# STM32F7.net
KiCad netlist of a schematic drawn in Altium Designer
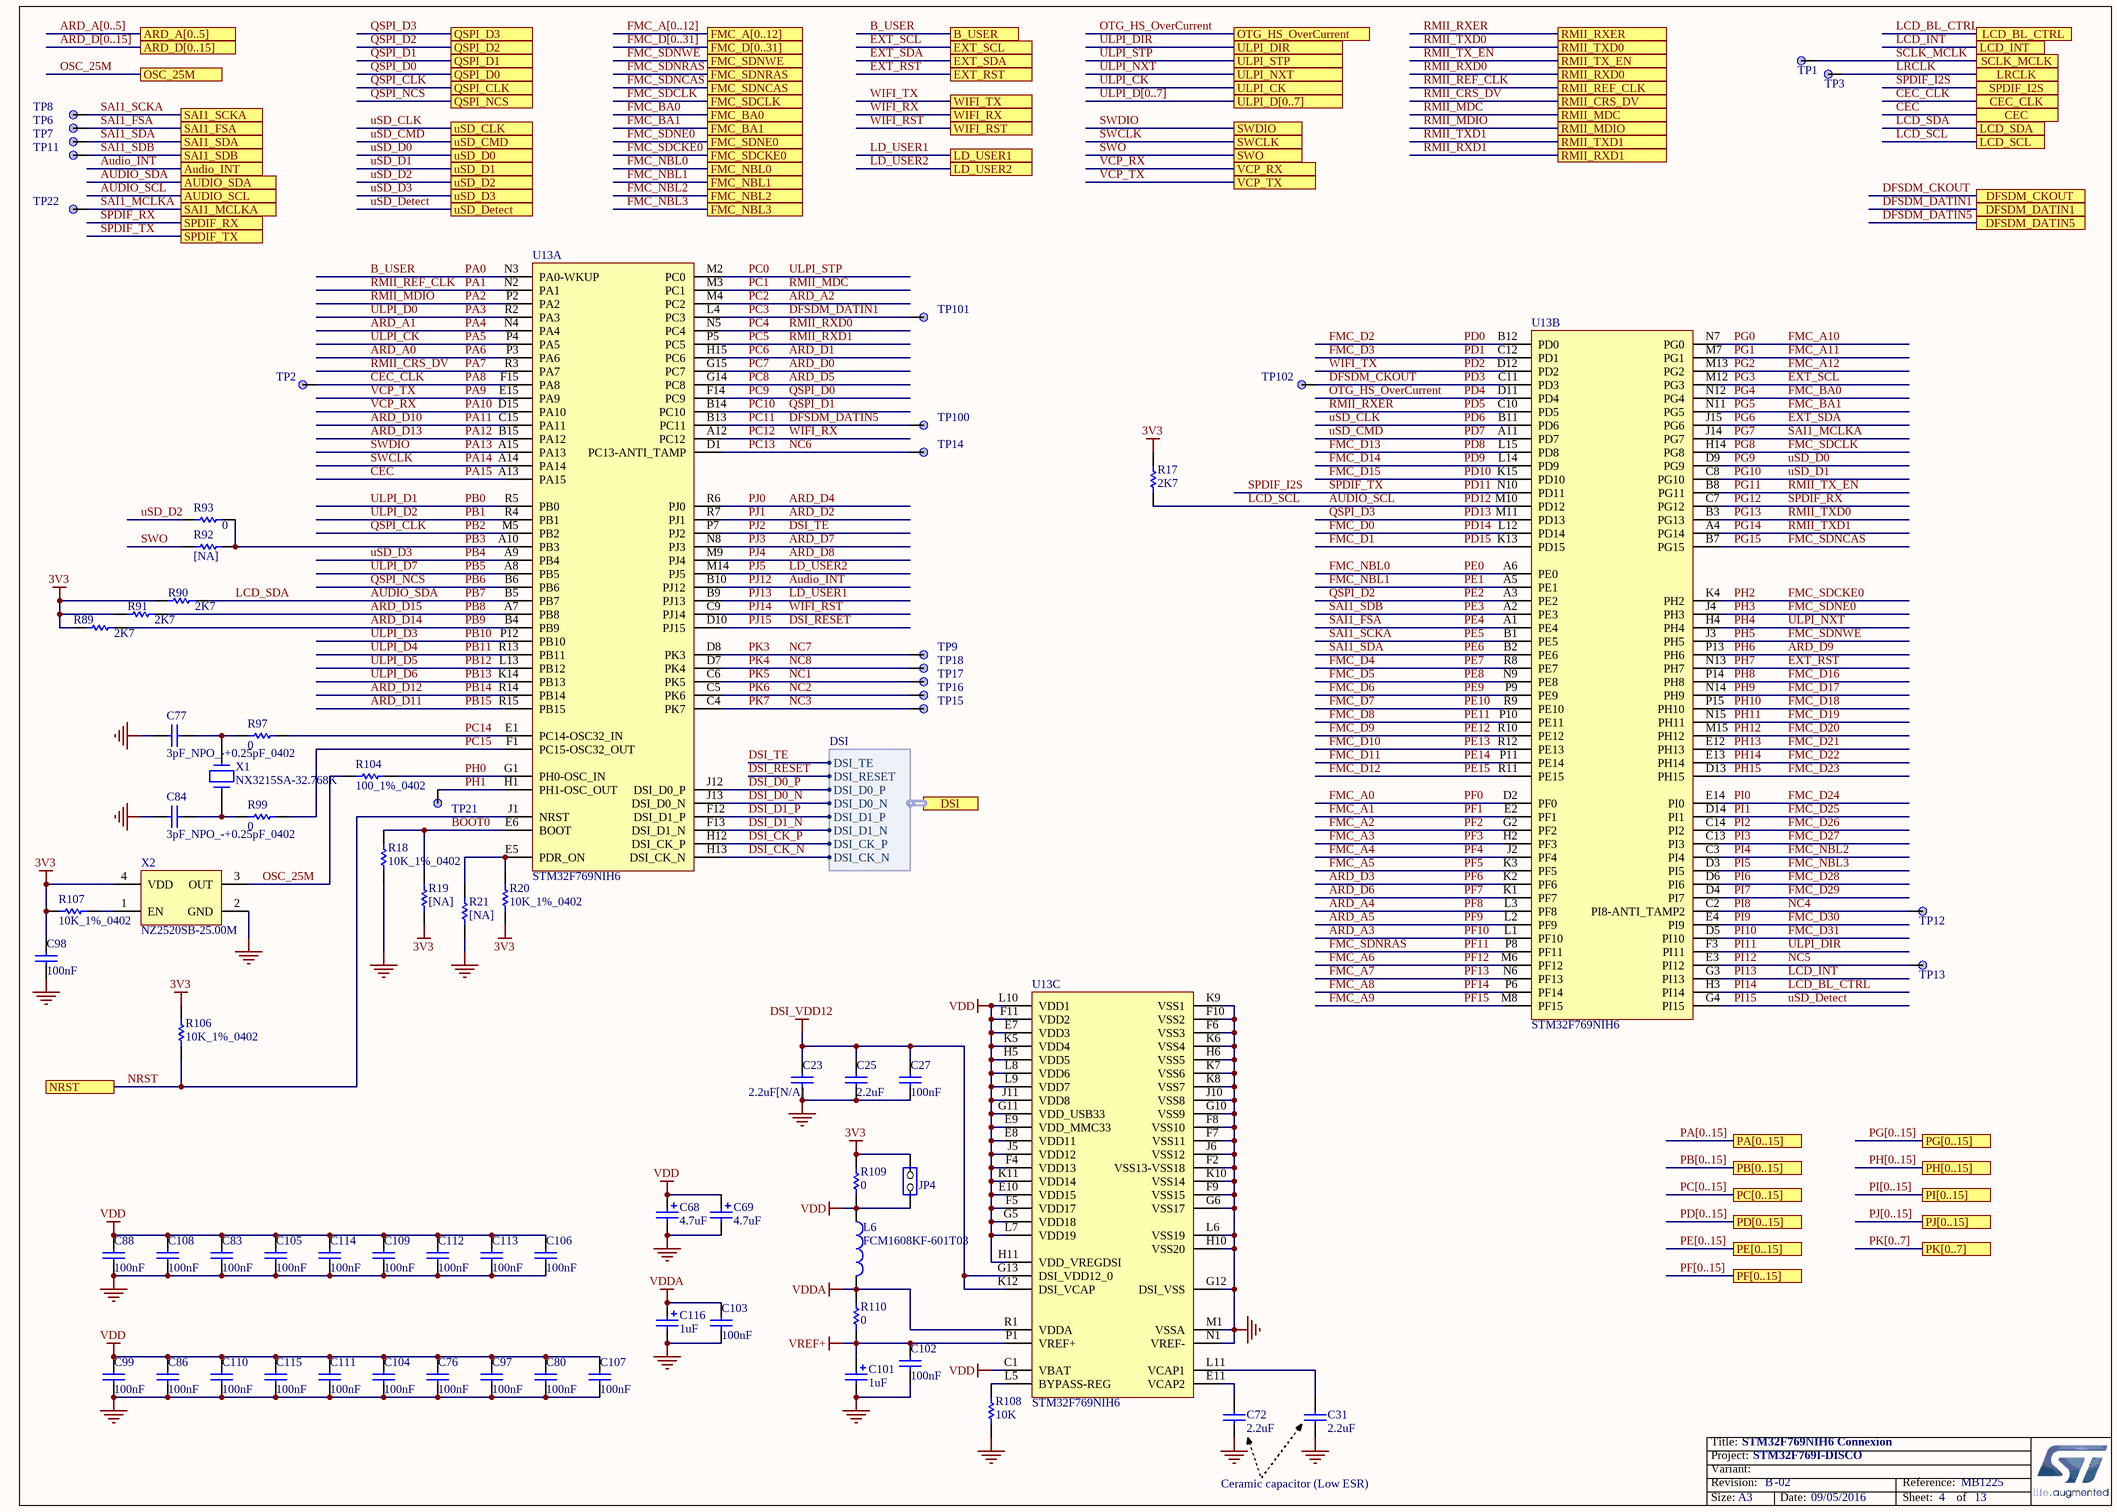
[diagram p0: STM32F7.SchDoc]

(export (version "E")
  (design (tool "Eeschema 10.0.6"))
  (components
    (comp (ref "C23")
      (value "2.2uF[N/A]")
      (footprint "1206C")
      (description "Capacitor,2.2uF,16V, X7R,10%,1206,YAGEO")
      (libsource (lib "MCD_TOOLS_CAPACITOR") (part "Cap_2.2uF_X7R_10%_1206"))
    )
    (comp (ref "C25")
      (value "2.2uF")
      (footprint "0603C")
      (description "Capacitor,2.2uF,10V, X5R,10%,0603,YAGEO")
      (libsource (lib "MCD_TOOLS_CAPACITOR") (part "Cap_2.2uF_X5R_10%_0603"))
    )
    (comp (ref "C27")
      (value "100nF")
      (footprint "0402C")
      (description "Capacitor,100nF,16V,X7R,10%,0402,YAGEO")
      (libsource (lib "MCD_TOOLS_CAPACITOR") (part "Cap_100nF_X7R_10%_0402"))
    )
    (comp (ref "C31")
      (value "2.2uF")
      (footprint "1206C")
      (description "Capacitor,2.2uF,16V, X7R,10%,1206,YAGEO")
      (libsource (lib "MCD_TOOLS") (part "Cap_2.2uF_X7R_10%_1206"))
    )
    (comp (ref "C68")
      (value "4.7uF")
      (footprint "TAN-A")
      (description "Polarized Capacitor,4.7uF,16V,10%,typeA,AVX")
      (libsource (lib "MCD_TOOLS") (part "Cap_4.7uF_POL_10%_TANA"))
    )
    (comp (ref "C69")
      (value "4.7uF")
      (footprint "TAN-A")
      (description "Polarized Capacitor,4.7uF,16V,10%,typeA,AVX")
      (libsource (lib "MCD_TOOLS") (part "Cap_4.7uF_POL_10%_TANA"))
    )
    (comp (ref "C72")
      (value "2.2uF")
      (footprint "1206C")
      (description "Capacitor,2.2uF,16V, X7R,10%,1206,YAGEO")
      (libsource (lib "MCD_TOOLS") (part "Cap_2.2uF_X7R_10%_1206"))
    )
    (comp (ref "C76")
      (value "100nF")
      (footprint "0402C")
      (description "Capacitor,100nF,16V,X7R,10%,0402,YAGEO")
      (libsource (lib "MCD_TOOLS") (part "Cap_100nF_X7R_10%_0402"))
    )
    (comp (ref "C77")
      (value "3pF_NPO_-+0.25pF_0402")
      (footprint "0402C")
      (description "Capacitor, 3pF, 16V, NPO, -+0.25pF, 0402, KEMET")
      (libsource (lib "MCD_TOOLS_CAPACITOR") (part "Cap_4.3pF_NPO_-+0.25pF_0402"))
    )
    (comp (ref "C80")
      (value "100nF")
      (footprint "0402C")
      (description "Capacitor,100nF,16V,X7R,10%,0402,YAGEO")
      (libsource (lib "MCD_TOOLS") (part "Cap_100nF_X7R_10%_0402"))
    )
    (comp (ref "C83")
      (value "100nF")
      (footprint "0402C")
      (description "Capacitor,100nF,16V,X7R,10%,0402,YAGEO")
      (libsource (lib "MCD_TOOLS") (part "Cap_100nF_X7R_10%_0402"))
    )
    (comp (ref "C84")
      (value "3pF_NPO_-+0.25pF_0402")
      (footprint "0402C")
      (description "Capacitor, 3pF, 16V, NPO, -+0.25pF, 0402, KEMET")
      (libsource (lib "MCD_TOOLS_CAPACITOR") (part "Cap_4.3pF_NPO_-+0.25pF_0402"))
    )
    (comp (ref "C86")
      (value "100nF")
      (footprint "0402C")
      (description "Capacitor,100nF,16V,X7R,10%,0402,YAGEO")
      (libsource (lib "MCD_TOOLS") (part "Cap_100nF_X7R_10%_0402"))
    )
    (comp (ref "C88")
      (value "100nF")
      (footprint "0402C")
      (description "Capacitor,100nF,16V,X7R,10%,0402,YAGEO")
      (libsource (lib "MCD_TOOLS") (part "Cap_100nF_X7R_10%_0402"))
    )
    (comp (ref "C97")
      (value "100nF")
      (footprint "0402C")
      (description "Capacitor,100nF,16V,X7R,10%,0402,YAGEO")
      (libsource (lib "MCD_TOOLS") (part "Cap_100nF_X7R_10%_0402"))
    )
    (comp (ref "C98")
      (value "100nF")
      (footprint "0402C")
      (description "Capacitor,100nF,16V,X7R,10%,0402,YAGEO")
      (libsource (lib "MCD_TOOLS") (part "Cap_100nF_X7R_10%_0402"))
    )
    (comp (ref "C99")
      (value "100nF")
      (footprint "0402C")
      (description "Capacitor,100nF,16V,X7R,10%,0402,YAGEO")
      (libsource (lib "MCD_TOOLS") (part "Cap_100nF_X7R_10%_0402"))
    )
    (comp (ref "C101")
      (value "1uF")
      (footprint "TAN-A")
      (description "Polarized Capacitor,1uF,16V,10%,typeA,AVX")
      (libsource (lib "MCD_TOOLS") (part "Cap_1uF_POL_10%_TANA"))
    )
    (comp (ref "C102")
      (value "100nF")
      (footprint "0402C")
      (description "Capacitor,100nF,16V,X7R,10%,0402,YAGEO")
      (libsource (lib "MCD_TOOLS") (part "Cap_100nF_X7R_10%_0402"))
    )
    (comp (ref "C103")
      (value "100nF")
      (footprint "0402C")
      (description "Capacitor,100nF,16V,X7R,10%,0402,YAGEO")
      (libsource (lib "MCD_TOOLS") (part "Cap_100nF_X7R_10%_0402"))
    )
    (comp (ref "C104")
      (value "100nF")
      (footprint "0402C")
      (description "Capacitor,100nF,16V,X7R,10%,0402,YAGEO")
      (libsource (lib "MCD_TOOLS") (part "Cap_100nF_X7R_10%_0402"))
    )
    (comp (ref "C105")
      (value "100nF")
      (footprint "0402C")
      (description "Capacitor,100nF,16V,X7R,10%,0402,YAGEO")
      (libsource (lib "MCD_TOOLS") (part "Cap_100nF_X7R_10%_0402"))
    )
    (comp (ref "C106")
      (value "100nF")
      (footprint "0402C")
      (description "Capacitor,100nF,16V,X7R,10%,0402,YAGEO")
      (libsource (lib "MCD_TOOLS") (part "Cap_100nF_X7R_10%_0402"))
    )
    (comp (ref "C107")
      (value "100nF")
      (footprint "0402C")
      (description "Capacitor,100nF,16V,X7R,10%,0402,YAGEO")
      (libsource (lib "MCD_TOOLS") (part "Cap_100nF_X7R_10%_0402"))
    )
    (comp (ref "C108")
      (value "100nF")
      (footprint "0402C")
      (description "Capacitor,100nF,16V,X7R,10%,0402,YAGEO")
      (libsource (lib "MCD_TOOLS") (part "Cap_100nF_X7R_10%_0402"))
    )
    (comp (ref "C109")
      (value "100nF")
      (footprint "0402C")
      (description "Capacitor,100nF,16V,X7R,10%,0402,YAGEO")
      (libsource (lib "MCD_TOOLS") (part "Cap_100nF_X7R_10%_0402"))
    )
    (comp (ref "C110")
      (value "100nF")
      (footprint "0402C")
      (description "Capacitor,100nF,16V,X7R,10%,0402,YAGEO")
      (libsource (lib "MCD_TOOLS") (part "Cap_100nF_X7R_10%_0402"))
    )
    (comp (ref "C111")
      (value "100nF")
      (footprint "0402C")
      (description "Capacitor,100nF,16V,X7R,10%,0402,YAGEO")
      (libsource (lib "MCD_TOOLS") (part "Cap_100nF_X7R_10%_0402"))
    )
    (comp (ref "C112")
      (value "100nF")
      (footprint "0402C")
      (description "Capacitor,100nF,16V,X7R,10%,0402,YAGEO")
      (libsource (lib "MCD_TOOLS") (part "Cap_100nF_X7R_10%_0402"))
    )
    (comp (ref "C113")
      (value "100nF")
      (footprint "0402C")
      (description "Capacitor,100nF,16V,X7R,10%,0402,YAGEO")
      (libsource (lib "MCD_TOOLS") (part "Cap_100nF_X7R_10%_0402"))
    )
    (comp (ref "C114")
      (value "100nF")
      (footprint "0402C")
      (description "Capacitor,100nF,16V,X7R,10%,0402,YAGEO")
      (libsource (lib "MCD_TOOLS") (part "Cap_100nF_X7R_10%_0402"))
    )
    (comp (ref "C115")
      (value "100nF")
      (footprint "0402C")
      (description "Capacitor,100nF,16V,X7R,10%,0402,YAGEO")
      (libsource (lib "MCD_TOOLS") (part "Cap_100nF_X7R_10%_0402"))
    )
    (comp (ref "C116")
      (value "1uF")
      (footprint "TAN-A")
      (description "Polarized Capacitor,1uF,16V,10%,typeA,AVX")
      (libsource (lib "MCD_TOOLS") (part "Cap_1uF_POL_10%_TANA"))
    )
    (comp (ref "JP4") (value "JP2") (footprint "SIP2") (libsource (lib "MCD_TOOLS_CONNECTOR") (part "JP2")))
    (comp (ref "L6")
      (value "FCM1608KF-601T03")
      (footprint "0603L")
      (description "Bead,600R,350mA,0603,FCM1608KF-601T03,Tai-tech")
      (libsource (lib "MCD_TOOLS") (part "BEAD_600R_350MA_0603"))
    )
    (comp (ref "R17")
      (value "2K7")
      (footprint "0402R")
      (description "Resistor,2K7,0402,1%,YAGEO")
      (libsource (lib "MCD_TOOLS") (part "Res_2K7_1%_0402"))
    )
    (comp (ref "R18")
      (value "10K_1%_0402")
      (footprint "0402R")
      (description "Resistor,10K,0402,1%,YAGEO")
      (libsource (lib "MCD_TOOLS") (part "Res_10K_1%_0402"))
    )
    (comp (ref "R19")
      (value "[NA]")
      (footprint "0402R")
      (description "Resistor,[NA],0402")
      (libsource (lib "MCD_TOOLS") (part "Res_NA_0402"))
    )
    (comp (ref "R20")
      (value "10K_1%_0402")
      (footprint "0402R")
      (description "Resistor,10K,0402,1%,YAGEO")
      (libsource (lib "MCD_TOOLS") (part "Res_10K_1%_0402"))
    )
    (comp (ref "R21")
      (value "[NA]")
      (footprint "0402R")
      (description "Resistor,[NA],0402")
      (libsource (lib "MCD_TOOLS") (part "Res_NA_0402"))
    )
    (comp (ref "R89")
      (value "2K7")
      (footprint "0402R")
      (description "Resistor,2K7,0402,1%,YAGEO")
      (libsource (lib "MCD_TOOLS") (part "Res_2K7_1%_0402"))
    )
    (comp (ref "R90")
      (value "2K7")
      (footprint "0402R")
      (description "Resistor,2K7,0402,1%,YAGEO")
      (libsource (lib "MCD_TOOLS") (part "Res_2K7_1%_0402"))
    )
    (comp (ref "R91")
      (value "2K7")
      (footprint "0402R")
      (description "Resistor,2K7,0402,1%,YAGEO")
      (libsource (lib "MCD_TOOLS") (part "Res_2K7_1%_0402"))
    )
    (comp (ref "R92")
      (value "[NA]")
      (footprint "0402R")
      (description "Resistor,[NA],0402")
      (libsource (lib "MCD_TOOLS_RESISTOR") (part "Res_NA_0402"))
    )
    (comp (ref "R93")
      (value "0")
      (footprint "0402R")
      (description "Resistor,0,0402,5%,YAGEO")
      (libsource (lib "MCD_TOOLS_RESISTOR") (part "Res_0_5%_0402"))
    )
    (comp (ref "R97")
      (value "0")
      (footprint "0402R")
      (description "Resistor,0,0402,5%,YAGEO")
      (libsource (lib "MCD_TOOLS") (part "Res_0_5%_0402"))
    )
    (comp (ref "R99")
      (value "0")
      (footprint "0402R")
      (description "Resistor,0,0402,5%,YAGEO")
      (libsource (lib "MCD_TOOLS") (part "Res_0_5%_0402"))
    )
    (comp (ref "R104")
      (value "100_1%_0402")
      (footprint "0402R")
      (description "Resistor,100,0402,1%,YAGEO")
      (libsource (lib "MCD_TOOLS") (part "Res_100_1%_0402"))
    )
    (comp (ref "R106")
      (value "10K_1%_0402")
      (footprint "0402R")
      (description "Resistor,10K,0402,1%,YAGEO")
      (libsource (lib "MCD_TOOLS") (part "Res_10K_1%_0402"))
    )
    (comp (ref "R107")
      (value "10K_1%_0402")
      (footprint "0402R")
      (description "Resistor,10K,0402,1%,YAGEO")
      (libsource (lib "MCD_TOOLS") (part "Res_10K_1%_0402"))
    )
    (comp (ref "R108")
      (value "10K")
      (footprint "0402R")
      (description "Resistor,10K,0402,1%,YAGEO")
      (libsource (lib "MCD_TOOLS") (part "Res_10K_1%_0402"))
    )
    (comp (ref "R109")
      (value "0")
      (footprint "0603R-GS")
      (description "Resistor,0,0603,5%,YAGEO")
      (libsource (lib "MCD_TOOLS") (part "Res_0_5%_0603"))
    )
    (comp (ref "R110")
      (value "0")
      (footprint "0603R-GS")
      (description "Resistor,0,0603,5%,YAGEO")
      (libsource (lib "MCD_TOOLS") (part "Res_0_5%_0603"))
    )
    (comp (ref "TP1")
      (value "TP")
      (footprint "TP_C40")
      (description "Test Point")
      (libsource (lib "MCD_TOOLS_CONNECTOR") (part "TP"))
    )
    (comp (ref "TP2")
      (value "TP")
      (footprint "TP_C40")
      (description "Test Point")
      (libsource (lib "MCD_TOOLS_CONNECTOR") (part "TP"))
    )
    (comp (ref "TP3")
      (value "TP")
      (footprint "TP_C40")
      (description "Test Point")
      (libsource (lib "MCD_TOOLS_CONNECTOR") (part "TP"))
    )
    (comp (ref "TP6")
      (value "TP")
      (footprint "TP_C40")
      (description "Test Point")
      (libsource (lib "MCD_TOOLS_CONNECTOR") (part "TP"))
    )
    (comp (ref "TP7")
      (value "TP")
      (footprint "TP_C40")
      (description "Test Point")
      (libsource (lib "MCD_TOOLS_CONNECTOR") (part "TP"))
    )
    (comp (ref "TP8")
      (value "TP")
      (footprint "TP_C40")
      (description "Test Point")
      (libsource (lib "MCD_TOOLS_CONNECTOR") (part "TP"))
    )
    (comp (ref "TP9")
      (value "TP")
      (footprint "TP_C40")
      (description "Test Point")
      (libsource (lib "MCD_TOOLS_CONNECTOR") (part "TP"))
    )
    (comp (ref "TP11")
      (value "TP")
      (footprint "TP_C40")
      (description "Test Point")
      (libsource (lib "MCD_TOOLS_CONNECTOR") (part "TP"))
    )
    (comp (ref "TP12")
      (value "TP")
      (footprint "TP_C40")
      (description "Test Point")
      (libsource (lib "MCD_TOOLS_CONNECTOR") (part "TP"))
    )
    (comp (ref "TP13")
      (value "TP")
      (footprint "TP_C40")
      (description "Test Point")
      (libsource (lib "MCD_TOOLS_CONNECTOR") (part "TP"))
    )
    (comp (ref "TP14")
      (value "TP")
      (footprint "TP_C40")
      (description "Test Point")
      (libsource (lib "MCD_TOOLS_CONNECTOR") (part "TP"))
    )
    (comp (ref "TP15")
      (value "TP")
      (footprint "TP_C40")
      (description "Test Point")
      (libsource (lib "MCD_TOOLS_CONNECTOR") (part "TP"))
    )
    (comp (ref "TP16")
      (value "TP")
      (footprint "TP_C40")
      (description "Test Point")
      (libsource (lib "MCD_TOOLS_CONNECTOR") (part "TP"))
    )
    (comp (ref "TP17")
      (value "TP")
      (footprint "TP_C40")
      (description "Test Point")
      (libsource (lib "MCD_TOOLS_CONNECTOR") (part "TP"))
    )
    (comp (ref "TP18")
      (value "TP")
      (footprint "TP_C40")
      (description "Test Point")
      (libsource (lib "MCD_TOOLS_CONNECTOR") (part "TP"))
    )
    (comp (ref "TP21")
      (value "TP")
      (footprint "TP_C40")
      (description "Test Point")
      (libsource (lib "MCD_TOOLS_CONNECTOR") (part "TP"))
    )
    (comp (ref "TP22")
      (value "TP")
      (footprint "TP_C40")
      (description "Test Point")
      (libsource (lib "MCD_TOOLS_CONNECTOR") (part "TP"))
    )
    (comp (ref "TP100")
      (value "TP")
      (footprint "TP_C40")
      (description "Test Point")
      (libsource (lib "MCD_TOOLS_CONNECTOR") (part "TP"))
    )
    (comp (ref "TP101")
      (value "TP")
      (footprint "TP_C40")
      (description "Test Point")
      (libsource (lib "MCD_TOOLS_CONNECTOR") (part "TP"))
    )
    (comp (ref "TP102")
      (value "TP")
      (footprint "TP_C40")
      (description "Test Point")
      (libsource (lib "MCD_TOOLS_CONNECTOR") (part "TP"))
    )
    (comp (ref "U13")
      (value "STM32F769NIH6")
      (footprint "BGA216_0R8_13X13")
      (description "STM32F769NIH6 (STM32F7 Big Birdie) TBGA216")
      (libsource (lib "MCD_TOOLS_MCU") (part "STM32F769NIH6U"))
    )
    (comp (ref "X1")
      (value "NX3215SA-32.768K")
      (footprint "XTAL_2SM_3R2X1R5")
      (description "Crystal 32.768kHz, 6pF, -+20PPM, R=50K, SMD")
      (libsource (lib "MCD_TOOLS") (part "XTAL_32K_NX3215SA"))
    )
    (comp (ref "X2")
      (value "NZ2520SB-25.00M")
      (footprint "OSC_4SM_2R5X2")
      (description "Oscillator 25.00Mhz, -+50PPM, 3.3V, Temp -55 to +125°C")
      (libsource (lib "MCD_TOOLS_MISCELLANEOUS") (part "OSC_25M_NZ2520SB"))
    )
  )
  (nets
    (net (code "11") (name "/ARD_A0") (class "Default")
      (node (ref "U13") (pin "P3") (pinfunction "PA6_P3") (pintype "passive"))
    )
    (net (code "12") (name "/ARD_A1") (class "Default")
      (node (ref "U13") (pin "N4") (pinfunction "PA4_N4") (pintype "passive"))
    )
    (net (code "13") (name "/ARD_A2") (class "Default")
      (node (ref "U13") (pin "M4") (pinfunction "PC2_M4") (pintype "passive"))
    )
    (net (code "14") (name "/ARD_A3") (class "Default")
      (node (ref "U13") (pin "L1") (pinfunction "PF10_L1") (pintype "passive"))
    )
    (net (code "15") (name "/ARD_A4") (class "Default")
      (node (ref "U13") (pin "L3") (pinfunction "PF8_L3") (pintype "passive"))
    )
    (net (code "16") (name "/ARD_A5") (class "Default")
      (node (ref "U13") (pin "L2") (pinfunction "PF9_L2") (pintype "passive"))
    )
    (net (code "18") (name "/ARD_D0") (class "Default")
      (node (ref "U13") (pin "G15") (pinfunction "PC7_G15") (pintype "passive"))
    )
    (net (code "19") (name "/ARD_D1") (class "Default")
      (node (ref "U13") (pin "H15") (pinfunction "PC6_H15") (pintype "passive"))
    )
    (net (code "20") (name "/ARD_D2") (class "Default")
      (node (ref "U13") (pin "R7") (pinfunction "PJ1_R7") (pintype "passive"))
    )
    (net (code "21") (name "/ARD_D3") (class "Default")
      (node (ref "U13") (pin "K2") (pinfunction "PF6_K2") (pintype "passive"))
    )
    (net (code "22") (name "/ARD_D4") (class "Default")
      (node (ref "U13") (pin "R6") (pinfunction "PJ0_R6") (pintype "passive"))
    )
    (net (code "23") (name "/ARD_D5") (class "Default")
      (node (ref "U13") (pin "G14") (pinfunction "PC8_G14") (pintype "passive"))
    )
    (net (code "24") (name "/ARD_D6") (class "Default")
      (node (ref "U13") (pin "K1") (pinfunction "PF7_K1") (pintype "passive"))
    )
    (net (code "25") (name "/ARD_D7") (class "Default")
      (node (ref "U13") (pin "N8") (pinfunction "PJ3_N8") (pintype "passive"))
    )
    (net (code "26") (name "/ARD_D8") (class "Default")
      (node (ref "U13") (pin "M9") (pinfunction "PJ4_M9") (pintype "passive"))
    )
    (net (code "27") (name "/ARD_D9") (class "Default")
      (node (ref "U13") (pin "P13") (pinfunction "PH6_P13") (pintype "passive"))
    )
    (net (code "28") (name "/ARD_D10") (class "Default")
      (node (ref "U13") (pin "C15") (pinfunction "PA11_C15") (pintype "passive"))
    )
    (net (code "29") (name "/ARD_D11") (class "Default")
      (node (ref "U13") (pin "R15") (pinfunction "PB15_R15") (pintype "passive"))
    )
    (net (code "30") (name "/ARD_D12") (class "Default")
      (node (ref "U13") (pin "R14") (pinfunction "PB14_R14") (pintype "passive"))
    )
    (net (code "31") (name "/ARD_D13") (class "Default")
      (node (ref "U13") (pin "B15") (pinfunction "PA12_B15") (pintype "passive"))
    )
    (net (code "32") (name "/ARD_D14") (class "Default")
      (node (ref "R89") (pin "2") (pinfunction "2_2") (pintype "passive"))
      (node (ref "U13") (pin "B4") (pinfunction "PB9_B4") (pintype "passive"))
    )
    (net (code "33") (name "/ARD_D15") (class "Default")
      (node (ref "R91") (pin "2") (pinfunction "2_2") (pintype "passive"))
      (node (ref "U13") (pin "A7") (pinfunction "PB8_A7") (pintype "passive"))
    )
    (net (code "35") (name "/BOOT0") (class "Default")
      (node (ref "R18") (pin "2") (pinfunction "2_2") (pintype "passive"))
      (node (ref "R19") (pin "2") (pinfunction "2_2") (pintype "passive"))
      (node (ref "U13") (pin "E6") (pinfunction "BOOT_E6") (pintype "passive"))
    )
    (net (code "36") (name "/DSI_CK_N") (class "Default")
      (node (ref "U13") (pin "H13") (pinfunction "DSI_CK_N_H13") (pintype "passive"))
    )
    (net (code "37") (name "/DSI_CK_P") (class "Default")
      (node (ref "U13") (pin "H12") (pinfunction "DSI_CK_P_H12") (pintype "passive"))
    )
    (net (code "38") (name "/DSI_D0_N") (class "Default")
      (node (ref "U13") (pin "J13") (pinfunction "DSI_D0_N_J13") (pintype "passive"))
    )
    (net (code "39") (name "/DSI_D0_P") (class "Default")
      (node (ref "U13") (pin "J12") (pinfunction "DSI_D0_P_J12") (pintype "passive"))
    )
    (net (code "40") (name "/DSI_D1_N") (class "Default")
      (node (ref "U13") (pin "F13") (pinfunction "DSI_D1_N_F13") (pintype "passive"))
    )
    (net (code "41") (name "/DSI_D1_P") (class "Default")
      (node (ref "U13") (pin "F12") (pinfunction "DSI_D1_P_F12") (pintype "passive"))
    )
    (net (code "42") (name "/FMC_A0") (class "Default")
      (node (ref "U13") (pin "D2") (pinfunction "PF0_D2") (pintype "passive"))
    )
    (net (code "43") (name "/FMC_A1") (class "Default")
      (node (ref "U13") (pin "E2") (pinfunction "PF1_E2") (pintype "passive"))
    )
    (net (code "44") (name "/FMC_A2") (class "Default")
      (node (ref "U13") (pin "G2") (pinfunction "PF2_G2") (pintype "passive"))
    )
    (net (code "45") (name "/FMC_A3") (class "Default")
      (node (ref "U13") (pin "H2") (pinfunction "PF3_H2") (pintype "passive"))
    )
    (net (code "46") (name "/FMC_A4") (class "Default")
      (node (ref "U13") (pin "J2") (pinfunction "PF4_J2") (pintype "passive"))
    )
    (net (code "47") (name "/FMC_A5") (class "Default")
      (node (ref "U13") (pin "K3") (pinfunction "PF5_K3") (pintype "passive"))
    )
    (net (code "48") (name "/FMC_A6") (class "Default")
      (node (ref "U13") (pin "M6") (pinfunction "PF12_M6") (pintype "passive"))
    )
    (net (code "49") (name "/FMC_A7") (class "Default")
      (node (ref "U13") (pin "N6") (pinfunction "PF13_N6") (pintype "passive"))
    )
    (net (code "50") (name "/FMC_A8") (class "Default")
      (node (ref "U13") (pin "P6") (pinfunction "PF14_P6") (pintype "passive"))
    )
    (net (code "51") (name "/FMC_A9") (class "Default")
      (node (ref "U13") (pin "M8") (pinfunction "PF15_M8") (pintype "passive"))
    )
    (net (code "52") (name "/FMC_A10") (class "Default")
      (node (ref "U13") (pin "N7") (pinfunction "PG0_N7") (pintype "passive"))
    )
    (net (code "53") (name "/FMC_A11") (class "Default")
      (node (ref "U13") (pin "M7") (pinfunction "PG1_M7") (pintype "passive"))
    )
    (net (code "54") (name "/FMC_A12") (class "Default")
      (node (ref "U13") (pin "M13") (pinfunction "PG2_M13") (pintype "passive"))
    )
    (net (code "56") (name "/FMC_D0") (class "Default")
      (node (ref "U13") (pin "L12") (pinfunction "PD14_L12") (pintype "passive"))
    )
    (net (code "57") (name "/FMC_D1") (class "Default")
      (node (ref "U13") (pin "K13") (pinfunction "PD15_K13") (pintype "passive"))
    )
    (net (code "58") (name "/FMC_D2") (class "Default")
      (node (ref "U13") (pin "B12") (pinfunction "PD0_B12") (pintype "passive"))
    )
    (net (code "59") (name "/FMC_D3") (class "Default")
      (node (ref "U13") (pin "C12") (pinfunction "PD1_C12") (pintype "passive"))
    )
    (net (code "60") (name "/FMC_D4") (class "Default")
      (node (ref "U13") (pin "R8") (pinfunction "PE7_R8") (pintype "passive"))
    )
    (net (code "61") (name "/FMC_D5") (class "Default")
      (node (ref "U13") (pin "N9") (pinfunction "PE8_N9") (pintype "passive"))
    )
    (net (code "62") (name "/FMC_D6") (class "Default")
      (node (ref "U13") (pin "P9") (pinfunction "PE9_P9") (pintype "passive"))
    )
    (net (code "63") (name "/FMC_D7") (class "Default")
      (node (ref "U13") (pin "R9") (pinfunction "PE10_R9") (pintype "passive"))
    )
    (net (code "64") (name "/FMC_D8") (class "Default")
      (node (ref "U13") (pin "P10") (pinfunction "PE11_P10") (pintype "passive"))
    )
    (net (code "65") (name "/FMC_D9") (class "Default")
      (node (ref "U13") (pin "R10") (pinfunction "PE12_R10") (pintype "passive"))
    )
    (net (code "66") (name "/FMC_D10") (class "Default")
      (node (ref "U13") (pin "R12") (pinfunction "PE13_R12") (pintype "passive"))
    )
    (net (code "67") (name "/FMC_D11") (class "Default")
      (node (ref "U13") (pin "P11") (pinfunction "PE14_P11") (pintype "passive"))
    )
    (net (code "68") (name "/FMC_D12") (class "Default")
      (node (ref "U13") (pin "R11") (pinfunction "PE15_R11") (pintype "passive"))
    )
    (net (code "69") (name "/FMC_D13") (class "Default")
      (node (ref "U13") (pin "L15") (pinfunction "PD8_L15") (pintype "passive"))
    )
    (net (code "70") (name "/FMC_D14") (class "Default")
      (node (ref "U13") (pin "L14") (pinfunction "PD9_L14") (pintype "passive"))
    )
    (net (code "71") (name "/FMC_D15") (class "Default")
      (node (ref "U13") (pin "K15") (pinfunction "PD10_K15") (pintype "passive"))
    )
    (net (code "72") (name "/FMC_D16") (class "Default")
      (node (ref "U13") (pin "P14") (pinfunction "PH8_P14") (pintype "passive"))
    )
    (net (code "73") (name "/FMC_D17") (class "Default")
      (node (ref "U13") (pin "N14") (pinfunction "PH9_N14") (pintype "passive"))
    )
    (net (code "74") (name "/FMC_D18") (class "Default")
      (node (ref "U13") (pin "P15") (pinfunction "PH10_P15") (pintype "passive"))
    )
    (net (code "75") (name "/FMC_D19") (class "Default")
      (node (ref "U13") (pin "N15") (pinfunction "PH11_N15") (pintype "passive"))
    )
    (net (code "76") (name "/FMC_D20") (class "Default")
      (node (ref "U13") (pin "M15") (pinfunction "PH12_M15") (pintype "passive"))
    )
    (net (code "77") (name "/FMC_D21") (class "Default")
      (node (ref "U13") (pin "E12") (pinfunction "PH13_E12") (pintype "passive"))
    )
    (net (code "78") (name "/FMC_D22") (class "Default")
      (node (ref "U13") (pin "E13") (pinfunction "PH14_E13") (pintype "passive"))
    )
    (net (code "79") (name "/FMC_D23") (class "Default")
      (node (ref "U13") (pin "D13") (pinfunction "PH15_D13") (pintype "passive"))
    )
    (net (code "80") (name "/FMC_D24") (class "Default")
      (node (ref "U13") (pin "E14") (pinfunction "PI0_E14") (pintype "passive"))
    )
    (net (code "81") (name "/FMC_D25") (class "Default")
      (node (ref "U13") (pin "D14") (pinfunction "PI1_D14") (pintype "passive"))
    )
    (net (code "82") (name "/FMC_D26") (class "Default")
      (node (ref "U13") (pin "C14") (pinfunction "PI2_C14") (pintype "passive"))
    )
    (net (code "83") (name "/FMC_D27") (class "Default")
      (node (ref "U13") (pin "C13") (pinfunction "PI3_C13") (pintype "passive"))
    )
    (net (code "84") (name "/FMC_D28") (class "Default")
      (node (ref "U13") (pin "D6") (pinfunction "PI6_D6") (pintype "passive"))
    )
    (net (code "85") (name "/FMC_D29") (class "Default")
      (node (ref "U13") (pin "D4") (pinfunction "PI7_D4") (pintype "passive"))
    )
    (net (code "86") (name "/FMC_D30") (class "Default")
      (node (ref "U13") (pin "E4") (pinfunction "PI9_E4") (pintype "passive"))
    )
    (net (code "87") (name "/FMC_D31") (class "Default")
      (node (ref "U13") (pin "D5") (pinfunction "PI10_D5") (pintype "passive"))
    )
    (net (code "89") (name "/LRCLK") (class "Default")
      (node (ref "TP3") (pin "1") (pinfunction "1_1") (pintype "passive"))
    )
    (net (code "90") (name "/NRST") (class "Default")
      (node (ref "R106") (pin "1") (pinfunction "1_1") (pintype "passive"))
      (node (ref "U13") (pin "J1") (pinfunction "NRST_J1") (pintype "passive"))
    )
    (net (code "91") (name "/OSC_25M") (class "Default")
      (node (ref "R104") (pin "1") (pinfunction "1_1") (pintype "passive"))
      (node (ref "X2") (pin "3") (pinfunction "OUT_3") (pintype "passive"))
    )
    (net (code "92") (name "/PA0") (class "Default")
      (node (ref "U13") (pin "N3") (pinfunction "PA0-WKUP_N3") (pintype "passive"))
    )
    (net (code "93") (name "/PA1") (class "Default")
      (node (ref "U13") (pin "N2") (pinfunction "PA1_N2") (pintype "passive"))
    )
    (net (code "94") (name "/PA2") (class "Default")
      (node (ref "U13") (pin "P2") (pinfunction "PA2_P2") (pintype "passive"))
    )
    (net (code "95") (name "/PA5") (class "Default")
      (node (ref "U13") (pin "P4") (pinfunction "PA5_P4") (pintype "passive"))
    )
    (net (code "96") (name "/PA7") (class "Default")
      (node (ref "U13") (pin "R3") (pinfunction "PA7_R3") (pintype "passive"))
    )
    (net (code "97") (name "/PA8") (class "Default")
      (node (ref "TP2") (pin "1") (pinfunction "1_1") (pintype "passive"))
      (node (ref "U13") (pin "F15") (pinfunction "PA8_F15") (pintype "passive"))
    )
    (net (code "98") (name "/PA9") (class "Default")
      (node (ref "U13") (pin "E15") (pinfunction "PA9_E15") (pintype "passive"))
    )
    (net (code "99") (name "/PA10") (class "Default")
      (node (ref "U13") (pin "D15") (pinfunction "PA10_D15") (pintype "passive"))
    )
    (net (code "100") (name "/PA13") (class "Default")
      (node (ref "U13") (pin "A15") (pinfunction "PA13_A15") (pintype "passive"))
    )
    (net (code "101") (name "/PA14") (class "Default")
      (node (ref "U13") (pin "A14") (pinfunction "PA14_A14") (pintype "passive"))
    )
    (net (code "102") (name "/PA15") (class "Default")
      (node (ref "U13") (pin "A13") (pinfunction "PA15_A13") (pintype "passive"))
    )
    (net (code "104") (name "/PB2") (class "Default")
      (node (ref "U13") (pin "M5") (pinfunction "PB2_M5") (pintype "passive"))
    )
    (net (code "105") (name "/PB3") (class "Default")
      (node (ref "R92") (pin "2") (pinfunction "2_2") (pintype "passive"))
      (node (ref "R93") (pin "2") (pinfunction "2_2") (pintype "passive"))
      (node (ref "U13") (pin "A10") (pinfunction "PB3_A10") (pintype "passive"))
    )
    (net (code "106") (name "/PB4") (class "Default")
      (node (ref "U13") (pin "A9") (pinfunction "PB4_A9") (pintype "passive"))
    )
    (net (code "107") (name "/PB6") (class "Default")
      (node (ref "U13") (pin "B6") (pinfunction "PB6_B6") (pintype "passive"))
    )
    (net (code "108") (name "/PB7") (class "Default")
      (node (ref "R90") (pin "2") (pinfunction "2_2") (pintype "passive"))
      (node (ref "U13") (pin "B5") (pinfunction "PB7_B5") (pintype "passive"))
    )
    (net (code "110") (name "/PC0") (class "Default")
      (node (ref "U13") (pin "M2") (pinfunction "PC0_M2") (pintype "passive"))
    )
    (net (code "111") (name "/PC1") (class "Default")
      (node (ref "U13") (pin "M3") (pinfunction "PC1_M3") (pintype "passive"))
    )
    (net (code "112") (name "/PC3") (class "Default")
      (node (ref "TP101") (pin "1") (pinfunction "1_1") (pintype "passive"))
      (node (ref "U13") (pin "L4") (pinfunction "PC3_L4") (pintype "passive"))
    )
    (net (code "113") (name "/PC4") (class "Default")
      (node (ref "U13") (pin "N5") (pinfunction "PC4_N5") (pintype "passive"))
    )
    (net (code "114") (name "/PC5") (class "Default")
      (node (ref "U13") (pin "P5") (pinfunction "PC5_P5") (pintype "passive"))
    )
    (net (code "115") (name "/PC9") (class "Default")
      (node (ref "U13") (pin "F14") (pinfunction "PC9_F14") (pintype "passive"))
    )
    (net (code "116") (name "/PC10") (class "Default")
      (node (ref "U13") (pin "B14") (pinfunction "PC10_B14") (pintype "passive"))
    )
    (net (code "117") (name "/PC11") (class "Default")
      (node (ref "TP100") (pin "1") (pinfunction "1_1") (pintype "passive"))
      (node (ref "U13") (pin "B13") (pinfunction "PC11_B13") (pintype "passive"))
    )
    (net (code "118") (name "/PC12") (class "Default")
      (node (ref "U13") (pin "A12") (pinfunction "PC12_A12") (pintype "passive"))
    )
    (net (code "119") (name "/PC13") (class "Default")
      (node (ref "TP14") (pin "1") (pinfunction "1_1") (pintype "passive"))
      (node (ref "U13") (pin "D1") (pinfunction "PC13-ANTI_TAMP_D1") (pintype "passive"))
    )
    (net (code "120") (name "/PC14") (class "Default")
      (node (ref "R97") (pin "2") (pinfunction "2_2") (pintype "passive"))
      (node (ref "U13") (pin "E1") (pinfunction "PC14-OSC32_IN_E1") (pintype "passive"))
    )
    (net (code "121") (name "/PC15") (class "Default")
      (node (ref "R99") (pin "2") (pinfunction "2_2") (pintype "passive"))
      (node (ref "U13") (pin "F1") (pinfunction "PC15-OSC32_OUT_F1") (pintype "passive"))
    )
    (net (code "123") (name "/PD2") (class "Default")
      (node (ref "U13") (pin "D12") (pinfunction "PD2_D12") (pintype "passive"))
    )
    (net (code "124") (name "/PD3") (class "Default")
      (node (ref "TP102") (pin "1") (pinfunction "1_1") (pintype "passive"))
      (node (ref "U13") (pin "C11") (pinfunction "PD3_C11") (pintype "passive"))
    )
    (net (code "125") (name "/PD4") (class "Default")
      (node (ref "U13") (pin "D11") (pinfunction "PD4_D11") (pintype "passive"))
    )
    (net (code "126") (name "/PD5") (class "Default")
      (node (ref "U13") (pin "C10") (pinfunction "PD5_C10") (pintype "passive"))
    )
    (net (code "127") (name "/PD6") (class "Default")
      (node (ref "U13") (pin "B11") (pinfunction "PD6_B11") (pintype "passive"))
    )
    (net (code "128") (name "/PD7") (class "Default")
      (node (ref "U13") (pin "A11") (pinfunction "PD7_A11") (pintype "passive"))
    )
    (net (code "129") (name "/PD11") (class "Default")
      (node (ref "U13") (pin "N10") (pinfunction "PD11_N10") (pintype "passive"))
    )
    (net (code "130") (name "/PD12") (class "Default")
      (node (ref "R17") (pin "1") (pinfunction "1_1") (pintype "passive"))
      (node (ref "U13") (pin "M10") (pinfunction "PD12_M10") (pintype "passive"))
    )
    (net (code "131") (name "/PD13") (class "Default")
      (node (ref "U13") (pin "M11") (pinfunction "PD13_M11") (pintype "passive"))
    )
    (net (code "133") (name "/PE0") (class "Default")
      (node (ref "U13") (pin "A6") (pinfunction "PE0_A6") (pintype "passive"))
    )
    (net (code "134") (name "/PE1") (class "Default")
      (node (ref "U13") (pin "A5") (pinfunction "PE1_A5") (pintype "passive"))
    )
    (net (code "135") (name "/PE2") (class "Default")
      (node (ref "U13") (pin "A3") (pinfunction "PE2_A3") (pintype "passive"))
    )
    (net (code "136") (name "/PE3") (class "Default")
      (node (ref "TP11") (pin "1") (pinfunction "1_1") (pintype "passive"))
      (node (ref "U13") (pin "A2") (pinfunction "PE3_A2") (pintype "passive"))
    )
    (net (code "137") (name "/PE4") (class "Default")
      (node (ref "TP6") (pin "1") (pinfunction "1_1") (pintype "passive"))
      (node (ref "U13") (pin "A1") (pinfunction "PE4_A1") (pintype "passive"))
    )
    (net (code "138") (name "/PE5") (class "Default")
      (node (ref "TP8") (pin "1") (pinfunction "1_1") (pintype "passive"))
      (node (ref "U13") (pin "B1") (pinfunction "PE5_B1") (pintype "passive"))
    )
    (net (code "139") (name "/PE6") (class "Default")
      (node (ref "TP7") (pin "1") (pinfunction "1_1") (pintype "passive"))
      (node (ref "U13") (pin "B2") (pinfunction "PE6_B2") (pintype "passive"))
    )
    (net (code "141") (name "/PF11") (class "Default")
      (node (ref "U13") (pin "P8") (pinfunction "PF11_P8") (pintype "passive"))
    )
    (net (code "143") (name "/PG3") (class "Default")
      (node (ref "U13") (pin "M12") (pinfunction "PG3_M12") (pintype "passive"))
    )
    (net (code "144") (name "/PG4") (class "Default")
      (node (ref "U13") (pin "N12") (pinfunction "PG4_N12") (pintype "passive"))
    )
    (net (code "145") (name "/PG5") (class "Default")
      (node (ref "U13") (pin "N11") (pinfunction "PG5_N11") (pintype "passive"))
    )
    (net (code "146") (name "/PG6") (class "Default")
      (node (ref "U13") (pin "J15") (pinfunction "PG6_J15") (pintype "passive"))
    )
    (net (code "147") (name "/PG7") (class "Default")
      (node (ref "TP22") (pin "1") (pinfunction "1_1") (pintype "passive"))
      (node (ref "U13") (pin "J14") (pinfunction "PG7_J14") (pintype "passive"))
    )
    (net (code "148") (name "/PG8") (class "Default")
      (node (ref "U13") (pin "H14") (pinfunction "PG8_H14") (pintype "passive"))
    )
    (net (code "149") (name "/PG9") (class "Default")
      (node (ref "U13") (pin "D9") (pinfunction "PG9_D9") (pintype "passive"))
    )
    (net (code "150") (name "/PG10") (class "Default")
      (node (ref "U13") (pin "C8") (pinfunction "PG10_C8") (pintype "passive"))
    )
    (net (code "151") (name "/PG11") (class "Default")
      (node (ref "U13") (pin "B8") (pinfunction "PG11_B8") (pintype "passive"))
    )
    (net (code "152") (name "/PG12") (class "Default")
      (node (ref "U13") (pin "C7") (pinfunction "PG12_C7") (pintype "passive"))
    )
    (net (code "153") (name "/PG13") (class "Default")
      (node (ref "U13") (pin "B3") (pinfunction "PG13_B3") (pintype "passive"))
    )
    (net (code "154") (name "/PG14") (class "Default")
      (node (ref "U13") (pin "A4") (pinfunction "PG14_A4") (pintype "passive"))
    )
    (net (code "155") (name "/PG15") (class "Default")
      (node (ref "U13") (pin "B7") (pinfunction "PG15_B7") (pintype "passive"))
    )
    (net (code "157") (name "/PH0") (class "Default")
      (node (ref "R104") (pin "2") (pinfunction "2_2") (pintype "passive"))
      (node (ref "U13") (pin "G1") (pinfunction "PH0-OSC_IN_G1") (pintype "passive"))
    )
    (net (code "158") (name "/PH1") (class "Default")
      (node (ref "TP21") (pin "1") (pinfunction "1_1") (pintype "passive"))
      (node (ref "U13") (pin "H1") (pinfunction "PH1-OSC_OUT_H1") (pintype "passive"))
    )
    (net (code "159") (name "/PH2") (class "Default")
      (node (ref "U13") (pin "K4") (pinfunction "PH2_K4") (pintype "passive"))
    )
    (net (code "160") (name "/PH3") (class "Default")
      (node (ref "U13") (pin "J4") (pinfunction "PH3_J4") (pintype "passive"))
    )
    (net (code "161") (name "/PH4") (class "Default")
      (node (ref "U13") (pin "H4") (pinfunction "PH4_H4") (pintype "passive"))
    )
    (net (code "162") (name "/PH5") (class "Default")
      (node (ref "U13") (pin "J3") (pinfunction "PH5_J3") (pintype "passive"))
    )
    (net (code "163") (name "/PH7") (class "Default")
      (node (ref "U13") (pin "N13") (pinfunction "PH7_N13") (pintype "passive"))
    )
    (net (code "165") (name "/PI4") (class "Default")
      (node (ref "U13") (pin "C3") (pinfunction "PI4_C3") (pintype "passive"))
    )
    (net (code "166") (name "/PI5") (class "Default")
      (node (ref "U13") (pin "D3") (pinfunction "PI5_D3") (pintype "passive"))
    )
    (net (code "167") (name "/PI8") (class "Default")
      (node (ref "TP12") (pin "1") (pinfunction "1_1") (pintype "passive"))
      (node (ref "U13") (pin "C2") (pinfunction "PI8-ANTI_TAMP2_C2") (pintype "passive"))
    )
    (net (code "168") (name "/PI11") (class "Default")
      (node (ref "U13") (pin "F3") (pinfunction "PI11_F3") (pintype "passive"))
    )
    (net (code "169") (name "/PI12") (class "Default")
      (node (ref "TP13") (pin "1") (pinfunction "1_1") (pintype "passive"))
      (node (ref "U13") (pin "E3") (pinfunction "PI12_E3") (pintype "passive"))
    )
    (net (code "170") (name "/PI13") (class "Default")
      (node (ref "U13") (pin "G3") (pinfunction "PI13_G3") (pintype "passive"))
    )
    (net (code "171") (name "/PI14") (class "Default")
      (node (ref "U13") (pin "H3") (pinfunction "PI14_H3") (pintype "passive"))
    )
    (net (code "172") (name "/PI15") (class "Default")
      (node (ref "U13") (pin "G4") (pinfunction "PI15_G4") (pintype "passive"))
    )
    (net (code "174") (name "/PJ2") (class "Default")
      (node (ref "U13") (pin "P7") (pinfunction "PJ2_P7") (pintype "passive"))
    )
    (net (code "175") (name "/PJ5") (class "Default")
      (node (ref "U13") (pin "M14") (pinfunction "PJ5_M14") (pintype "passive"))
    )
    (net (code "176") (name "/PJ12") (class "Default")
      (node (ref "U13") (pin "B10") (pinfunction "PJ12_B10") (pintype "passive"))
    )
    (net (code "177") (name "/PJ13") (class "Default")
      (node (ref "U13") (pin "B9") (pinfunction "PJ13_B9") (pintype "passive"))
    )
    (net (code "178") (name "/PJ14") (class "Default")
      (node (ref "U13") (pin "C9") (pinfunction "PJ14_C9") (pintype "passive"))
    )
    (net (code "179") (name "/PJ15") (class "Default")
      (node (ref "U13") (pin "D10") (pinfunction "PJ15_D10") (pintype "passive"))
    )
    (net (code "181") (name "/PK3") (class "Default")
      (node (ref "TP9") (pin "1") (pinfunction "1_1") (pintype "passive"))
      (node (ref "U13") (pin "D8") (pinfunction "PK3_D8") (pintype "passive"))
    )
    (net (code "182") (name "/PK4") (class "Default")
      (node (ref "TP18") (pin "1") (pinfunction "1_1") (pintype "passive"))
      (node (ref "U13") (pin "D7") (pinfunction "PK4_D7") (pintype "passive"))
    )
    (net (code "183") (name "/PK5") (class "Default")
      (node (ref "TP17") (pin "1") (pinfunction "1_1") (pintype "passive"))
      (node (ref "U13") (pin "C6") (pinfunction "PK5_C6") (pintype "passive"))
    )
    (net (code "184") (name "/PK6") (class "Default")
      (node (ref "TP16") (pin "1") (pinfunction "1_1") (pintype "passive"))
      (node (ref "U13") (pin "C5") (pinfunction "PK6_C5") (pintype "passive"))
    )
    (net (code "185") (name "/PK7") (class "Default")
      (node (ref "TP15") (pin "1") (pinfunction "1_1") (pintype "passive"))
      (node (ref "U13") (pin "C4") (pinfunction "PK7_C4") (pintype "passive"))
    )
    (net (code "187") (name "/SCLK_MCLK") (class "Default")
      (node (ref "TP1") (pin "1") (pinfunction "1_1") (pintype "passive"))
    )
    (net (code "188") (name "/SWO") (class "Default")
      (node (ref "R92") (pin "1") (pinfunction "1_1") (pintype "passive"))
    )
    (net (code "189") (name "/ULPI_D0") (class "Default")
      (node (ref "U13") (pin "R2") (pinfunction "PA3_R2") (pintype "passive"))
    )
    (net (code "190") (name "/ULPI_D1") (class "Default")
      (node (ref "U13") (pin "R5") (pinfunction "PB0_R5") (pintype "passive"))
    )
    (net (code "191") (name "/ULPI_D2") (class "Default")
      (node (ref "U13") (pin "R4") (pinfunction "PB1_R4") (pintype "passive"))
    )
    (net (code "192") (name "/ULPI_D3") (class "Default")
      (node (ref "U13") (pin "P12") (pinfunction "PB10_P12") (pintype "passive"))
    )
    (net (code "193") (name "/ULPI_D4") (class "Default")
      (node (ref "U13") (pin "R13") (pinfunction "PB11_R13") (pintype "passive"))
    )
    (net (code "194") (name "/ULPI_D5") (class "Default")
      (node (ref "U13") (pin "L13") (pinfunction "PB12_L13") (pintype "passive"))
    )
    (net (code "195") (name "/ULPI_D6") (class "Default")
      (node (ref "U13") (pin "K14") (pinfunction "PB13_K14") (pintype "passive"))
    )
    (net (code "196") (name "/ULPI_D7") (class "Default")
      (node (ref "U13") (pin "A8") (pinfunction "PB5_A8") (pintype "passive"))
    )
    (net (code "198") (name "/uSD_D2") (class "Default")
      (node (ref "R93") (pin "1") (pinfunction "1_1") (pintype "passive"))
    )
    (net (code "200") (name "3V3") (class "Default")
      (node (ref "C98") (pin "2") (pinfunction "2_2") (pintype "passive"))
      (node (ref "JP4") (pin "2") (pinfunction "NO_2") (pintype "passive"))
      (node (ref "R106") (pin "2") (pinfunction "2_2") (pintype "passive"))
      (node (ref "R107") (pin "1") (pinfunction "1_1") (pintype "passive"))
      (node (ref "R109") (pin "2") (pinfunction "2_2") (pintype "passive"))
      (node (ref "R17") (pin "2") (pinfunction "2_2") (pintype "passive"))
      (node (ref "R19") (pin "1") (pinfunction "1_1") (pintype "passive"))
      (node (ref "R20") (pin "1") (pinfunction "1_1") (pintype "passive"))
      (node (ref "R89") (pin "1") (pinfunction "1_1") (pintype "passive"))
      (node (ref "R90") (pin "1") (pinfunction "1_1") (pintype "passive"))
      (node (ref "R91") (pin "1") (pinfunction "1_1") (pintype "passive"))
      (node (ref "X2") (pin "4") (pinfunction "VDD_4") (pintype "passive"))
    )
    (net (code "201") (name "DSI_VDD12") (class "Default")
      (node (ref "C23") (pin "2") (pinfunction "2_2") (pintype "passive"))
      (node (ref "C25") (pin "2") (pinfunction "2_2") (pintype "passive"))
      (node (ref "C27") (pin "2") (pinfunction "2_2") (pintype "passive"))
      (node (ref "U13") (pin "G13") (pinfunction "DSI_VDD12_0_G13") (pintype "power_in"))
      (node (ref "U13") (pin "K12") (pinfunction "DSI_VCAP_K12") (pintype "power_in"))
    )
    (net (code "202") (name "GND") (class "Default")
      (node (ref "C101") (pin "2") (pinfunction "2_2") (pintype "passive"))
      (node (ref "C102") (pin "1") (pinfunction "1_1") (pintype "passive"))
      (node (ref "C103") (pin "1") (pinfunction "1_1") (pintype "passive"))
      (node (ref "C104") (pin "1") (pinfunction "1_1") (pintype "passive"))
      (node (ref "C105") (pin "1") (pinfunction "1_1") (pintype "passive"))
      (node (ref "C106") (pin "1") (pinfunction "1_1") (pintype "passive"))
      (node (ref "C107") (pin "1") (pinfunction "1_1") (pintype "passive"))
      (node (ref "C108") (pin "1") (pinfunction "1_1") (pintype "passive"))
      (node (ref "C109") (pin "1") (pinfunction "1_1") (pintype "passive"))
      (node (ref "C110") (pin "1") (pinfunction "1_1") (pintype "passive"))
      (node (ref "C111") (pin "1") (pinfunction "1_1") (pintype "passive"))
      (node (ref "C112") (pin "1") (pinfunction "1_1") (pintype "passive"))
      (node (ref "C113") (pin "1") (pinfunction "1_1") (pintype "passive"))
      (node (ref "C114") (pin "1") (pinfunction "1_1") (pintype "passive"))
      (node (ref "C115") (pin "1") (pinfunction "1_1") (pintype "passive"))
      (node (ref "C116") (pin "2") (pinfunction "2_2") (pintype "passive"))
      (node (ref "C23") (pin "1") (pinfunction "1_1") (pintype "passive"))
      (node (ref "C25") (pin "1") (pinfunction "1_1") (pintype "passive"))
      (node (ref "C27") (pin "1") (pinfunction "1_1") (pintype "passive"))
      (node (ref "C31") (pin "1") (pinfunction "1_1") (pintype "passive"))
      (node (ref "C68") (pin "2") (pinfunction "2_2") (pintype "passive"))
      (node (ref "C69") (pin "2") (pinfunction "2_2") (pintype "passive"))
      (node (ref "C72") (pin "1") (pinfunction "1_1") (pintype "passive"))
      (node (ref "C76") (pin "1") (pinfunction "1_1") (pintype "passive"))
      (node (ref "C77") (pin "1") (pinfunction "1_1") (pintype "passive"))
      (node (ref "C80") (pin "1") (pinfunction "1_1") (pintype "passive"))
      (node (ref "C83") (pin "1") (pinfunction "1_1") (pintype "passive"))
      (node (ref "C84") (pin "1") (pinfunction "1_1") (pintype "passive"))
      (node (ref "C86") (pin "1") (pinfunction "1_1") (pintype "passive"))
      (node (ref "C88") (pin "1") (pinfunction "1_1") (pintype "passive"))
      (node (ref "C97") (pin "1") (pinfunction "1_1") (pintype "passive"))
      (node (ref "C98") (pin "1") (pinfunction "1_1") (pintype "passive"))
      (node (ref "C99") (pin "1") (pinfunction "1_1") (pintype "passive"))
      (node (ref "R108") (pin "1") (pinfunction "1_1") (pintype "passive"))
      (node (ref "R18") (pin "1") (pinfunction "1_1") (pintype "passive"))
      (node (ref "R21") (pin "1") (pinfunction "1_1") (pintype "passive"))
      (node (ref "U13") (pin "F10") (pinfunction "VSS2_F10") (pintype "passive"))
      (node (ref "U13") (pin "F2") (pinfunction "VSS13-VSS18_F2") (pintype "passive"))
      (node (ref "U13") (pin "F6") (pinfunction "VSS3_F6") (pintype "passive"))
      (node (ref "U13") (pin "F7") (pinfunction "VSS11_F7") (pintype "passive"))
      (node (ref "U13") (pin "F8") (pinfunction "VSS10_F8") (pintype "passive"))
      (node (ref "U13") (pin "F9") (pinfunction "VSS15_F9") (pintype "passive"))
      (node (ref "U13") (pin "G10") (pinfunction "VSS9_G10") (pintype "passive"))
      (node (ref "U13") (pin "G12") (pinfunction "DSI_VSS_G12") (pintype "power_in"))
      (node (ref "U13") (pin "G6") (pinfunction "VSS17_G6") (pintype "passive"))
      (node (ref "U13") (pin "H10") (pinfunction "VSS20_H10") (pintype "passive"))
      (node (ref "U13") (pin "H6") (pinfunction "VSS5_H6") (pintype "passive"))
      (node (ref "U13") (pin "J10") (pinfunction "VSS8_J10") (pintype "passive"))
      (node (ref "U13") (pin "J6") (pinfunction "VSS12_J6") (pintype "passive"))
      (node (ref "U13") (pin "K10") (pinfunction "VSS14_K10") (pintype "passive"))
      (node (ref "U13") (pin "K6") (pinfunction "VSS4_K6") (pintype "passive"))
      (node (ref "U13") (pin "K7") (pinfunction "VSS6_K7") (pintype "passive"))
      (node (ref "U13") (pin "K8") (pinfunction "VSS7_K8") (pintype "passive"))
      (node (ref "U13") (pin "K9") (pinfunction "VSS1_K9") (pintype "passive"))
      (node (ref "U13") (pin "L6") (pinfunction "VSS19_L6") (pintype "passive"))
      (node (ref "U13") (pin "M1") (pinfunction "VSSA_M1") (pintype "passive"))
      (node (ref "U13") (pin "N1") (pinfunction "VREF-_N1") (pintype "passive"))
      (node (ref "X2") (pin "2") (pinfunction "GND_2") (pintype "passive"))
    )
    (net (code "203") (name "Net-(C77-Pad2)") (class "Default")
      (node (ref "C77") (pin "2") (pinfunction "2_2") (pintype "passive"))
      (node (ref "R97") (pin "1") (pinfunction "1_1") (pintype "passive"))
      (node (ref "X1") (pin "1") (pinfunction "1_1") (pintype "passive"))
    )
    (net (code "204") (name "Net-(C84-Pad2)") (class "Default")
      (node (ref "C84") (pin "2") (pinfunction "2_2") (pintype "passive"))
      (node (ref "R99") (pin "1") (pinfunction "1_1") (pintype "passive"))
      (node (ref "X1") (pin "2") (pinfunction "2_2") (pintype "passive"))
    )
    (net (code "205") (name "Net-(U13A-PDR_ON)") (class "Default")
      (node (ref "R20") (pin "2") (pinfunction "2_2") (pintype "passive"))
      (node (ref "R21") (pin "2") (pinfunction "2_2") (pintype "passive"))
      (node (ref "U13") (pin "E5") (pinfunction "PDR_ON_E5") (pintype "passive"))
    )
    (net (code "206") (name "Net-(U13C-BYPASS-REG)") (class "Default")
      (node (ref "R108") (pin "2") (pinfunction "2_2") (pintype "passive"))
      (node (ref "U13") (pin "L5") (pinfunction "BYPASS-REG_L5") (pintype "passive"))
    )
    (net (code "207") (name "Net-(U13C-VCAP1)") (class "Default")
      (node (ref "C31") (pin "2") (pinfunction "2_2") (pintype "passive"))
      (node (ref "U13") (pin "L11") (pinfunction "VCAP1_L11") (pintype "passive"))
    )
    (net (code "208") (name "Net-(U13C-VCAP2)") (class "Default")
      (node (ref "C72") (pin "2") (pinfunction "2_2") (pintype "passive"))
      (node (ref "U13") (pin "E11") (pinfunction "VCAP2_E11") (pintype "passive"))
    )
    (net (code "209") (name "Net-(X2-EN)") (class "Default")
      (node (ref "R107") (pin "2") (pinfunction "2_2") (pintype "passive"))
      (node (ref "X2") (pin "1") (pinfunction "EN_1") (pintype "passive"))
    )
    (net (code "210") (name "VDD") (class "Default")
      (node (ref "C104") (pin "2") (pinfunction "2_2") (pintype "passive"))
      (node (ref "C105") (pin "2") (pinfunction "2_2") (pintype "passive"))
      (node (ref "C106") (pin "2") (pinfunction "2_2") (pintype "passive"))
      (node (ref "C107") (pin "2") (pinfunction "2_2") (pintype "passive"))
      (node (ref "C108") (pin "2") (pinfunction "2_2") (pintype "passive"))
      (node (ref "C109") (pin "2") (pinfunction "2_2") (pintype "passive"))
      (node (ref "C110") (pin "2") (pinfunction "2_2") (pintype "passive"))
      (node (ref "C111") (pin "2") (pinfunction "2_2") (pintype "passive"))
      (node (ref "C112") (pin "2") (pinfunction "2_2") (pintype "passive"))
      (node (ref "C113") (pin "2") (pinfunction "2_2") (pintype "passive"))
      (node (ref "C114") (pin "2") (pinfunction "2_2") (pintype "passive"))
      (node (ref "C115") (pin "2") (pinfunction "2_2") (pintype "passive"))
      (node (ref "C68") (pin "1") (pinfunction "1_1") (pintype "passive"))
      (node (ref "C69") (pin "1") (pinfunction "1_1") (pintype "passive"))
      (node (ref "C76") (pin "2") (pinfunction "2_2") (pintype "passive"))
      (node (ref "C80") (pin "2") (pinfunction "2_2") (pintype "passive"))
      (node (ref "C83") (pin "2") (pinfunction "2_2") (pintype "passive"))
      (node (ref "C86") (pin "2") (pinfunction "2_2") (pintype "passive"))
      (node (ref "C88") (pin "2") (pinfunction "2_2") (pintype "passive"))
      (node (ref "C97") (pin "2") (pinfunction "2_2") (pintype "passive"))
      (node (ref "C99") (pin "2") (pinfunction "2_2") (pintype "passive"))
      (node (ref "JP4") (pin "1") (pinfunction "COMMON_1") (pintype "passive"))
      (node (ref "L6") (pin "1") (pinfunction "1_1") (pintype "passive"))
      (node (ref "R109") (pin "1") (pinfunction "1_1") (pintype "passive"))
      (node (ref "U13") (pin "C1") (pinfunction "VBAT_C1") (pintype "passive"))
      (node (ref "U13") (pin "E10") (pinfunction "VDD15_E10") (pintype "passive"))
      (node (ref "U13") (pin "E7") (pinfunction "VDD3_E7") (pintype "passive"))
      (node (ref "U13") (pin "E8") (pinfunction "VDD11_E8") (pintype "passive"))
      (node (ref "U13") (pin "E9") (pinfunction "VDD_MMC33_E9") (pintype "passive"))
      (node (ref "U13") (pin "F11") (pinfunction "VDD2_F11") (pintype "passive"))
      (node (ref "U13") (pin "F4") (pinfunction "VDD13_F4") (pintype "passive"))
      (node (ref "U13") (pin "F5") (pinfunction "VDD17_F5") (pintype "passive"))
      (node (ref "U13") (pin "G11") (pinfunction "VDD_USB33_G11") (pintype "passive"))
      (node (ref "U13") (pin "G5") (pinfunction "VDD18_G5") (pintype "passive"))
      (node (ref "U13") (pin "H11") (pinfunction "VDD_VREGDSI_H11") (pintype "passive"))
      (node (ref "U13") (pin "H5") (pinfunction "VDD5_H5") (pintype "passive"))
      (node (ref "U13") (pin "J11") (pinfunction "VDD8_J11") (pintype "passive"))
      (node (ref "U13") (pin "J5") (pinfunction "VDD12_J5") (pintype "passive"))
      (node (ref "U13") (pin "K11") (pinfunction "VDD14_K11") (pintype "passive"))
      (node (ref "U13") (pin "K5") (pinfunction "VDD4_K5") (pintype "passive"))
      (node (ref "U13") (pin "L10") (pinfunction "VDD1_L10") (pintype "passive"))
      (node (ref "U13") (pin "L7") (pinfunction "VDD19_L7") (pintype "passive"))
      (node (ref "U13") (pin "L8") (pinfunction "VDD6_L8") (pintype "passive"))
      (node (ref "U13") (pin "L9") (pinfunction "VDD7_L9") (pintype "passive"))
    )
    (net (code "211") (name "VDDA") (class "Default")
      (node (ref "C103") (pin "2") (pinfunction "2_2") (pintype "passive"))
      (node (ref "C116") (pin "1") (pinfunction "1_1") (pintype "passive"))
      (node (ref "L6") (pin "2") (pinfunction "2_2") (pintype "passive"))
      (node (ref "R110") (pin "1") (pinfunction "1_1") (pintype "passive"))
      (node (ref "U13") (pin "R1") (pinfunction "VDDA_R1") (pintype "passive"))
    )
    (net (code "212") (name "VREF+") (class "Default")
      (node (ref "C101") (pin "1") (pinfunction "1_1") (pintype "passive"))
      (node (ref "C102") (pin "2") (pinfunction "2_2") (pintype "passive"))
      (node (ref "R110") (pin "2") (pinfunction "2_2") (pintype "passive"))
      (node (ref "U13") (pin "P1") (pinfunction "VREF+_P1") (pintype "passive"))
    )
  )
)
